# USB_FIFO.net
KiCad netlist of a schematic drawn in Altium Designer
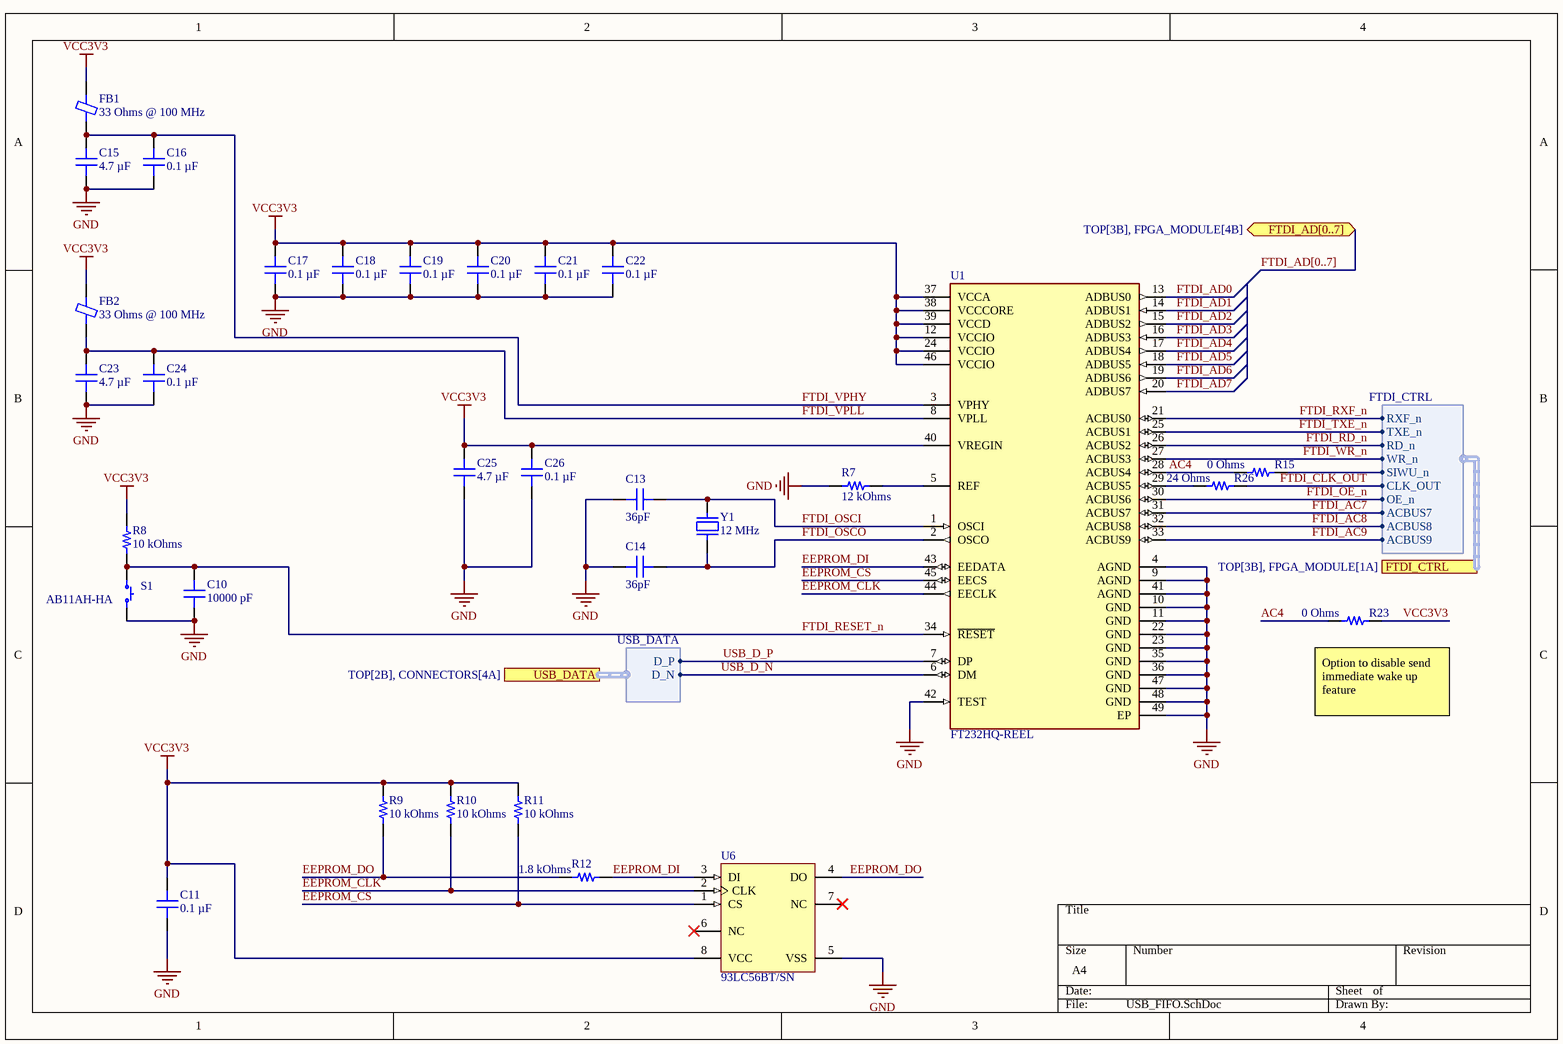
[diagram p0: USB_FIFO.SchDoc]

(export (version "E")
  (design (tool "Eeschema 10.0.6"))
  (components
    (comp (ref "C10")
      (value "10000 pF")
      (footprint "CAP 0402_1005")
      (description "CAP MLCC 0.01UF 100V X7R 0402")
      (fields (field (name "PART NUMBER") "HMK105B7103KVHFE") (field (name "MANUFACTURER") "Taiyo Yuden"))
      (libsource (lib "Celestial") (part "Capacitor"))
    )
    (comp (ref "C11")
      (value "0.1 µF")
      (footprint "CAP 0402_1005")
      (description "CAP CER 0.1UF 50V X5R 0402")
      (fields
        (field (name "PART NUMBER") "CGA2B3X5R1H104M050BB")
        (field (name "MANUFACTURER") "TDK Corporation")
      )
      (libsource (lib "Celestial") (part "Capacitor"))
    )
    (comp (ref "C13")
      (value "36pF")
      (footprint "CAP 0603_1608")
      (description "CAP CER 36PF 100V NP0 0603")
      (fields (field (name "PART NUMBER") "06031A360JAT2A") (field (name "MANUFACTURER") "AVX Corporation"))
      (libsource (lib "Celestial") (part "Capacitor"))
    )
    (comp (ref "C14")
      (value "36pF")
      (footprint "CAP 0603_1608")
      (description "CAP CER 36PF 100V NP0 0603")
      (fields (field (name "PART NUMBER") "06031A360JAT2A") (field (name "MANUFACTURER") "AVX Corporation"))
      (libsource (lib "Celestial") (part "Capacitor"))
    )
    (comp (ref "C15")
      (value "4.7 µF")
      (footprint "CAP 0402_1005")
      (description "CAP CER 4.7UF 16V X5R 0402")
      (fields
        (field (name "PART NUMBER") "CL05A475MO5NUNC")
        (field (name "MANUFACTURER") "Samsung Electro-Mechanics")
      )
      (libsource (lib "Celestial") (part "Capacitor"))
    )
    (comp (ref "C16")
      (value "0.1 µF")
      (footprint "CAP 0402_1005")
      (description "CAP CER 0.1UF 50V X5R 0402")
      (fields
        (field (name "PART NUMBER") "CGA2B3X5R1H104M050BB")
        (field (name "MANUFACTURER") "TDK Corporation")
      )
      (libsource (lib "Celestial") (part "Capacitor"))
    )
    (comp (ref "C17")
      (value "0.1 µF")
      (footprint "CAP 0402_1005")
      (description "CAP CER 0.1UF 50V X5R 0402")
      (fields
        (field (name "PART NUMBER") "CGA2B3X5R1H104M050BB")
        (field (name "MANUFACTURER") "TDK Corporation")
      )
      (libsource (lib "Celestial") (part "Capacitor"))
    )
    (comp (ref "C18")
      (value "0.1 µF")
      (footprint "CAP 0402_1005")
      (description "CAP CER 0.1UF 50V X5R 0402")
      (fields
        (field (name "PART NUMBER") "CGA2B3X5R1H104M050BB")
        (field (name "MANUFACTURER") "TDK Corporation")
      )
      (libsource (lib "Celestial") (part "Capacitor"))
    )
    (comp (ref "C19")
      (value "0.1 µF")
      (footprint "CAP 0402_1005")
      (description "CAP CER 0.1UF 50V X5R 0402")
      (fields
        (field (name "PART NUMBER") "CGA2B3X5R1H104M050BB")
        (field (name "MANUFACTURER") "TDK Corporation")
      )
      (libsource (lib "Celestial") (part "Capacitor"))
    )
    (comp (ref "C20")
      (value "0.1 µF")
      (footprint "CAP 0402_1005")
      (description "CAP CER 0.1UF 50V X5R 0402")
      (fields
        (field (name "PART NUMBER") "CGA2B3X5R1H104M050BB")
        (field (name "MANUFACTURER") "TDK Corporation")
      )
      (libsource (lib "Celestial") (part "Capacitor"))
    )
    (comp (ref "C21")
      (value "0.1 µF")
      (footprint "CAP 0402_1005")
      (description "CAP CER 0.1UF 50V X5R 0402")
      (fields
        (field (name "PART NUMBER") "CGA2B3X5R1H104M050BB")
        (field (name "MANUFACTURER") "TDK Corporation")
      )
      (libsource (lib "Celestial") (part "Capacitor"))
    )
    (comp (ref "C22")
      (value "0.1 µF")
      (footprint "CAP 0402_1005")
      (description "CAP CER 0.1UF 50V X5R 0402")
      (fields
        (field (name "PART NUMBER") "CGA2B3X5R1H104M050BB")
        (field (name "MANUFACTURER") "TDK Corporation")
      )
      (libsource (lib "Celestial") (part "Capacitor"))
    )
    (comp (ref "C23")
      (value "4.7 µF")
      (footprint "CAP 0402_1005")
      (description "CAP CER 4.7UF 16V X5R 0402")
      (fields
        (field (name "PART NUMBER") "CL05A475MO5NUNC")
        (field (name "MANUFACTURER") "Samsung Electro-Mechanics")
      )
      (libsource (lib "Celestial") (part "Capacitor"))
    )
    (comp (ref "C24")
      (value "0.1 µF")
      (footprint "CAP 0402_1005")
      (description "CAP CER 0.1UF 50V X5R 0402")
      (fields
        (field (name "PART NUMBER") "CGA2B3X5R1H104M050BB")
        (field (name "MANUFACTURER") "TDK Corporation")
      )
      (libsource (lib "Celestial") (part "Capacitor"))
    )
    (comp (ref "C25")
      (value "4.7 µF")
      (footprint "CAP 0402_1005")
      (description "CAP CER 4.7UF 16V X5R 0402")
      (fields
        (field (name "PART NUMBER") "CL05A475MO5NUNC")
        (field (name "MANUFACTURER") "Samsung Electro-Mechanics")
      )
      (libsource (lib "Celestial") (part "Capacitor"))
    )
    (comp (ref "C26")
      (value "0.1 µF")
      (footprint "CAP 0402_1005")
      (description "CAP CER 0.1UF 50V X5R 0402")
      (fields
        (field (name "PART NUMBER") "CGA2B3X5R1H104M050BB")
        (field (name "MANUFACTURER") "TDK Corporation")
      )
      (libsource (lib "Celestial") (part "Capacitor"))
    )
    (comp (ref "FB1")
      (value "33 Ohms @ 100 MHz")
      (footprint "FER 0201_0603")
      (description "FERRITE BEAD 33 OHM 0201 1LN")
      (fields (field (name "PART NUMBER") "MMZ0603F330CT000") (field (name "MANUFACTURER") "TDK Corporation"))
      (libsource (lib "Celestial") (part "Ferrite Chip"))
    )
    (comp (ref "FB2")
      (value "33 Ohms @ 100 MHz")
      (footprint "FER 0201_0603")
      (description "FERRITE BEAD 33 OHM 0201 1LN")
      (fields (field (name "PART NUMBER") "MMZ0603F330CT000") (field (name "MANUFACTURER") "TDK Corporation"))
      (libsource (lib "Celestial") (part "Ferrite Chip"))
    )
    (comp (ref "R7")
      (value "12 kOhms")
      (footprint "RES 0402_1005")
      (description "RES SMD 12K OHM 0.1% 1/16W 0402")
      (fields
        (field (name "PART NUMBER") "CPF0402B12KE1")
        (field (name "MANUFACTURER") "TE Connectivity Passive Product")
      )
      (libsource (lib "Celestial") (part "Resistor"))
    )
    (comp (ref "R8")
      (value "10 kOhms")
      (footprint "RES 0402_1005")
      (description "RES 10K OHM 0.1% 1/10W 0402")
      (fields
        (field (name "PART NUMBER") "RP73PF1E10KBTD")
        (field (name "MANUFACTURER") "TE Connectivity Passive Product")
      )
      (libsource (lib "Celestial") (part "Resistor"))
    )
    (comp (ref "R9")
      (value "10 kOhms")
      (footprint "RES 0402_1005")
      (description "RES 10K OHM 0.1% 1/10W 0402")
      (fields
        (field (name "PART NUMBER") "RP73PF1E10KBTD")
        (field (name "MANUFACTURER") "TE Connectivity Passive Product")
      )
      (libsource (lib "Celestial") (part "Resistor"))
    )
    (comp (ref "R10")
      (value "10 kOhms")
      (footprint "RES 0402_1005")
      (description "RES 10K OHM 0.1% 1/10W 0402")
      (fields
        (field (name "PART NUMBER") "RP73PF1E10KBTD")
        (field (name "MANUFACTURER") "TE Connectivity Passive Product")
      )
      (libsource (lib "Celestial") (part "Resistor"))
    )
    (comp (ref "R11")
      (value "10 kOhms")
      (footprint "RES 0402_1005")
      (description "RES 10K OHM 0.1% 1/10W 0402")
      (fields
        (field (name "PART NUMBER") "RP73PF1E10KBTD")
        (field (name "MANUFACTURER") "TE Connectivity Passive Product")
      )
      (libsource (lib "Celestial") (part "Resistor"))
    )
    (comp (ref "R12")
      (value "1.8 kOhms")
      (footprint "RES 0402_1005")
      (description "RES 1.8K OHM 1% 1/16W 0402")
      (fields (field (name "PART NUMBER") "RC0402FR-071K8L") (field (name "MANUFACTURER") "Yageo"))
      (libsource (lib "Celestial") (part "Resistor"))
    )
    (comp (ref "R15")
      (value "0 Ohms")
      (footprint "RES 0603_1608")
      (description "RES SMD 0 OHM JUMPER 1/2W 0603")
      (fields (field (name "PART NUMBER") "5110") (field (name "MANUFACTURER") "Keystone Electronics"))
      (libsource (lib "Celestial") (part "Resistor"))
    )
    (comp (ref "R23")
      (value "0 Ohms")
      (footprint "RES 0603_1608")
      (description "RES SMD 0 OHM JUMPER 1/2W 0603")
      (fields (field (name "PART NUMBER") "5110") (field (name "MANUFACTURER") "Keystone Electronics"))
      (libsource (lib "Celestial") (part "Resistor"))
    )
    (comp (ref "R26")
      (value "24 Ohms")
      (footprint "RES 0402_1005")
      (description "RES 24 OHM 1% 1/16W 0402")
      (fields (field (name "PART NUMBER") "RC0402FR-0724RL") (field (name "MANUFACTURER") "Yageo"))
      (libsource (lib "Celestial") (part "Resistor"))
    )
    (comp (ref "S1")
      (value "AB11AH-HA")
      (footprint "NKK AB11AH-HA")
      (description "SWITCH PUSH SPST-NO 0.4VA 28V")
      (fields (field (name "MANUFACTURER") "NKK Switches"))
      (libsource (lib "Celestial") (part "NKK AB11AH-HA"))
    )
    (comp (ref "U1")
      (value "FT232HQ-REEL")
      (footprint "FP-QFN-48-MFG")
      (description "IC HS USB TO UART/FIFO 48QFN")
      (libsource (lib "Altium Content Vault") (part "fcec249c9a260fcc9294b92a8e8e315"))
    )
    (comp (ref "U6")
      (value "93LC56BT/SN")
      (footprint "SOIC-SN8_M")
      (libsource (lib "Altium Content Vault") (part "MEM-SEEPROM-93AA46B-P-8"))
    )
    (comp (ref "Y1")
      (value "12 MHz")
      (footprint "ABRACON ABLS")
      (description "CRYSTAL 12.0000MHZ 20PF SMD")
      (fields
        (field (name "PART NUMBER") "ABLS-12.000MHZ-20-B-3-H-T")
        (field (name "MANUFACTURER") "Abracon LLC")
      )
      (libsource (lib "Celestial") (part "Abracon Crystal ABLS"))
    )
  )
  (nets
    (net (code "3") (name "/AC4") (class "Default")
      (node (ref "R15") (pin "1") (pinfunction "1_1") (pintype "passive"))
      (node (ref "R23") (pin "1") (pinfunction "1_1") (pintype "passive"))
      (node (ref "U1") (pin "28") (pinfunction "ACBUS4_28") (pintype "bidirectional"))
    )
    (net (code "4") (name "/EEPROM_CLK") (class "Default")
      (node (ref "R10") (pin "1") (pinfunction "1_1") (pintype "passive"))
      (node (ref "U1") (pin "44") (pinfunction "EECLK_44") (pintype "output"))
      (node (ref "U6") (pin "2") (pinfunction "CLK_2") (pintype "input"))
    )
    (net (code "5") (name "/EEPROM_CS") (class "Default")
      (node (ref "R11") (pin "1") (pinfunction "1_1") (pintype "passive"))
      (node (ref "U1") (pin "45") (pinfunction "EECS_45") (pintype "bidirectional"))
      (node (ref "U6") (pin "1") (pinfunction "CS_1") (pintype "input"))
    )
    (net (code "6") (name "/EEPROM_DI") (class "Default")
      (node (ref "R12") (pin "2") (pinfunction "2_2") (pintype "passive"))
      (node (ref "U1") (pin "43") (pinfunction "EEDATA_43") (pintype "bidirectional"))
      (node (ref "U6") (pin "3") (pinfunction "DI_3") (pintype "input"))
    )
    (net (code "7") (name "/EEPROM_DO") (class "Default")
      (node (ref "R12") (pin "1") (pinfunction "1_1") (pintype "passive"))
      (node (ref "R9") (pin "1") (pinfunction "1_1") (pintype "passive"))
      (node (ref "U6") (pin "4") (pinfunction "DO_4") (pintype "tri_state"))
    )
    (net (code "8") (name "/FTDI_AC7") (class "Default")
      (node (ref "U1") (pin "31") (pinfunction "ACBUS7_31") (pintype "bidirectional"))
    )
    (net (code "9") (name "/FTDI_AC8") (class "Default")
      (node (ref "U1") (pin "32") (pinfunction "ACBUS8_32") (pintype "bidirectional"))
    )
    (net (code "10") (name "/FTDI_AC9") (class "Default")
      (node (ref "U1") (pin "33") (pinfunction "ACBUS9_33") (pintype "bidirectional"))
    )
    (net (code "11") (name "/FTDI_AD0") (class "Default")
      (node (ref "U1") (pin "13") (pinfunction "ADBUS0_13") (pintype "output"))
    )
    (net (code "12") (name "/FTDI_AD1") (class "Default")
      (node (ref "U1") (pin "14") (pinfunction "ADBUS1_14") (pintype "input"))
    )
    (net (code "13") (name "/FTDI_AD2") (class "Default")
      (node (ref "U1") (pin "15") (pinfunction "ADBUS2_15") (pintype "output"))
    )
    (net (code "14") (name "/FTDI_AD3") (class "Default")
      (node (ref "U1") (pin "16") (pinfunction "ADBUS3_16") (pintype "input"))
    )
    (net (code "15") (name "/FTDI_AD4") (class "Default")
      (node (ref "U1") (pin "17") (pinfunction "ADBUS4_17") (pintype "output"))
    )
    (net (code "16") (name "/FTDI_AD5") (class "Default")
      (node (ref "U1") (pin "18") (pinfunction "ADBUS5_18") (pintype "input"))
    )
    (net (code "17") (name "/FTDI_AD6") (class "Default")
      (node (ref "U1") (pin "19") (pinfunction "ADBUS6_19") (pintype "output"))
    )
    (net (code "18") (name "/FTDI_AD7") (class "Default")
      (node (ref "U1") (pin "20") (pinfunction "ADBUS7_20") (pintype "input"))
    )
    (net (code "20") (name "/FTDI_CLK_OUT") (class "Default")
      (node (ref "R26") (pin "2") (pinfunction "2_2") (pintype "passive"))
    )
    (net (code "21") (name "/FTDI_OE_n") (class "Default")
      (node (ref "U1") (pin "30") (pinfunction "ACBUS6_30") (pintype "bidirectional"))
    )
    (net (code "22") (name "/FTDI_OSCI") (class "Default")
      (node (ref "C13") (pin "2") (pinfunction "2_2") (pintype "passive"))
      (node (ref "U1") (pin "1") (pinfunction "OSCI_1") (pintype "input"))
      (node (ref "Y1") (pin "2") (pinfunction "2_2") (pintype "passive"))
    )
    (net (code "23") (name "/FTDI_OSCO") (class "Default")
      (node (ref "C14") (pin "2") (pinfunction "2_2") (pintype "passive"))
      (node (ref "U1") (pin "2") (pinfunction "OSCO_2") (pintype "output"))
      (node (ref "Y1") (pin "1") (pinfunction "1_1") (pintype "passive"))
    )
    (net (code "24") (name "/FTDI_RD_n") (class "Default")
      (node (ref "U1") (pin "26") (pinfunction "ACBUS2_26") (pintype "bidirectional"))
    )
    (net (code "25") (name "/FTDI_RESET_n") (class "Default")
      (node (ref "C10") (pin "2") (pinfunction "2_2") (pintype "passive"))
      (node (ref "R8") (pin "1") (pinfunction "1_1") (pintype "passive"))
      (node (ref "S1") (pin "3") (pinfunction "3_3") (pintype "passive"))
      (node (ref "U1") (pin "34") (pinfunction "~{RESET}_34") (pintype "input"))
    )
    (net (code "26") (name "/FTDI_RXF_n") (class "Default")
      (node (ref "U1") (pin "21") (pinfunction "ACBUS0_21") (pintype "bidirectional"))
    )
    (net (code "27") (name "/FTDI_TXE_n") (class "Default")
      (node (ref "U1") (pin "25") (pinfunction "ACBUS1_25") (pintype "bidirectional"))
    )
    (net (code "28") (name "/FTDI_VPHY") (class "Default")
      (node (ref "C15") (pin "2") (pinfunction "2_2") (pintype "passive"))
      (node (ref "C16") (pin "2") (pinfunction "2_2") (pintype "passive"))
      (node (ref "FB1") (pin "1") (pinfunction "1_1") (pintype "passive"))
      (node (ref "U1") (pin "3") (pinfunction "VPHY_3") (pintype "power_in"))
    )
    (net (code "29") (name "/FTDI_VPLL") (class "Default")
      (node (ref "C23") (pin "2") (pinfunction "2_2") (pintype "passive"))
      (node (ref "C24") (pin "2") (pinfunction "2_2") (pintype "passive"))
      (node (ref "FB2") (pin "1") (pinfunction "1_1") (pintype "passive"))
      (node (ref "U1") (pin "8") (pinfunction "VPLL_8") (pintype "power_in"))
    )
    (net (code "30") (name "/FTDI_WR_n") (class "Default")
      (node (ref "U1") (pin "27") (pinfunction "ACBUS3_27") (pintype "bidirectional"))
    )
    (net (code "31") (name "/SIWU_n") (class "Default")
      (node (ref "R15") (pin "2") (pinfunction "2_2") (pintype "passive"))
    )
    (net (code "32") (name "/USB_D_N") (class "Default")
      (node (ref "U1") (pin "6") (pinfunction "DM_6") (pintype "bidirectional"))
    )
    (net (code "33") (name "/USB_D_P") (class "Default")
      (node (ref "U1") (pin "7") (pinfunction "DP_7") (pintype "bidirectional"))
    )
    (net (code "36") (name "GND") (class "Default")
      (node (ref "C10") (pin "1") (pinfunction "1_1") (pintype "passive"))
      (node (ref "C11") (pin "1") (pinfunction "1_1") (pintype "passive"))
      (node (ref "C13") (pin "1") (pinfunction "1_1") (pintype "passive"))
      (node (ref "C14") (pin "1") (pinfunction "1_1") (pintype "passive"))
      (node (ref "C15") (pin "1") (pinfunction "1_1") (pintype "passive"))
      (node (ref "C16") (pin "1") (pinfunction "1_1") (pintype "passive"))
      (node (ref "C17") (pin "1") (pinfunction "1_1") (pintype "passive"))
      (node (ref "C18") (pin "1") (pinfunction "1_1") (pintype "passive"))
      (node (ref "C19") (pin "1") (pinfunction "1_1") (pintype "passive"))
      (node (ref "C20") (pin "1") (pinfunction "1_1") (pintype "passive"))
      (node (ref "C21") (pin "1") (pinfunction "1_1") (pintype "passive"))
      (node (ref "C22") (pin "1") (pinfunction "1_1") (pintype "passive"))
      (node (ref "C23") (pin "1") (pinfunction "1_1") (pintype "passive"))
      (node (ref "C24") (pin "1") (pinfunction "1_1") (pintype "passive"))
      (node (ref "C25") (pin "1") (pinfunction "1_1") (pintype "passive"))
      (node (ref "C26") (pin "1") (pinfunction "1_1") (pintype "passive"))
      (node (ref "R7") (pin "1") (pinfunction "1_1") (pintype "passive"))
      (node (ref "S1") (pin "1") (pinfunction "1_1") (pintype "passive"))
      (node (ref "U1") (pin "10") (pinfunction "GND_10") (pintype "power_in"))
      (node (ref "U1") (pin "11") (pinfunction "GND_11") (pintype "power_in"))
      (node (ref "U1") (pin "22") (pinfunction "GND_22") (pintype "power_in"))
      (node (ref "U1") (pin "23") (pinfunction "GND_23") (pintype "power_in"))
      (node (ref "U1") (pin "35") (pinfunction "GND_35") (pintype "power_in"))
      (node (ref "U1") (pin "36") (pinfunction "GND_36") (pintype "power_in"))
      (node (ref "U1") (pin "4") (pinfunction "AGND_4") (pintype "power_in"))
      (node (ref "U1") (pin "41") (pinfunction "AGND_41") (pintype "power_in"))
      (node (ref "U1") (pin "42") (pinfunction "TEST_42") (pintype "input"))
      (node (ref "U1") (pin "47") (pinfunction "GND_47") (pintype "power_in"))
      (node (ref "U1") (pin "48") (pinfunction "GND_48") (pintype "power_in"))
      (node (ref "U1") (pin "49") (pinfunction "EP_49") (pintype "passive"))
      (node (ref "U1") (pin "9") (pinfunction "AGND_9") (pintype "power_in"))
      (node (ref "U6") (pin "5") (pinfunction "VSS_5") (pintype "power_in"))
    )
    (net (code "37") (name "Net-(U1-ACBUS5)") (class "Default")
      (node (ref "R26") (pin "1") (pinfunction "1_1") (pintype "passive"))
      (node (ref "U1") (pin "29") (pinfunction "ACBUS5_29") (pintype "bidirectional"))
    )
    (net (code "38") (name "Net-(U1-REF)") (class "Default")
      (node (ref "R7") (pin "2") (pinfunction "2_2") (pintype "passive"))
      (node (ref "U1") (pin "5") (pinfunction "REF_5") (pintype "passive"))
    )
    (net (code "39") (name "VCC3V3") (class "Default")
      (node (ref "C11") (pin "2") (pinfunction "2_2") (pintype "passive"))
      (node (ref "C17") (pin "2") (pinfunction "2_2") (pintype "passive"))
      (node (ref "C18") (pin "2") (pinfunction "2_2") (pintype "passive"))
      (node (ref "C19") (pin "2") (pinfunction "2_2") (pintype "passive"))
      (node (ref "C20") (pin "2") (pinfunction "2_2") (pintype "passive"))
      (node (ref "C21") (pin "2") (pinfunction "2_2") (pintype "passive"))
      (node (ref "C22") (pin "2") (pinfunction "2_2") (pintype "passive"))
      (node (ref "C25") (pin "2") (pinfunction "2_2") (pintype "passive"))
      (node (ref "C26") (pin "2") (pinfunction "2_2") (pintype "passive"))
      (node (ref "FB1") (pin "2") (pinfunction "2_2") (pintype "passive"))
      (node (ref "FB2") (pin "2") (pinfunction "2_2") (pintype "passive"))
      (node (ref "R10") (pin "2") (pinfunction "2_2") (pintype "passive"))
      (node (ref "R11") (pin "2") (pinfunction "2_2") (pintype "passive"))
      (node (ref "R23") (pin "2") (pinfunction "2_2") (pintype "passive"))
      (node (ref "R8") (pin "2") (pinfunction "2_2") (pintype "passive"))
      (node (ref "R9") (pin "2") (pinfunction "2_2") (pintype "passive"))
      (node (ref "U1") (pin "12") (pinfunction "VCCIO_12") (pintype "power_in"))
      (node (ref "U1") (pin "24") (pinfunction "VCCIO_24") (pintype "power_in"))
      (node (ref "U1") (pin "37") (pinfunction "VCCA_37") (pintype "power_in"))
      (node (ref "U1") (pin "38") (pinfunction "VCCCORE_38") (pintype "power_in"))
      (node (ref "U1") (pin "39") (pinfunction "VCCD_39") (pintype "power_in"))
      (node (ref "U1") (pin "40") (pinfunction "VREGIN_40") (pintype "power_in"))
      (node (ref "U1") (pin "46") (pinfunction "VCCIO_46") (pintype "power_in"))
      (node (ref "U6") (pin "8") (pinfunction "VCC_8") (pintype "power_in"))
    )
    (net (code "40") (name "unconnected-(U6-NC-Pad6)") (class "Default")
      (node (ref "U6") (pin "6") (pinfunction "NC_6") (pintype "passive+no_connect"))
    )
    (net (code "41") (name "unconnected-(U6-NC-Pad7)") (class "Default")
      (node (ref "U6") (pin "7") (pinfunction "NC_7") (pintype "passive+no_connect"))
    )
  )
)
